# ACS770_breakout_v0_1.net
KiCad netlist of a schematic drawn in EAGLE
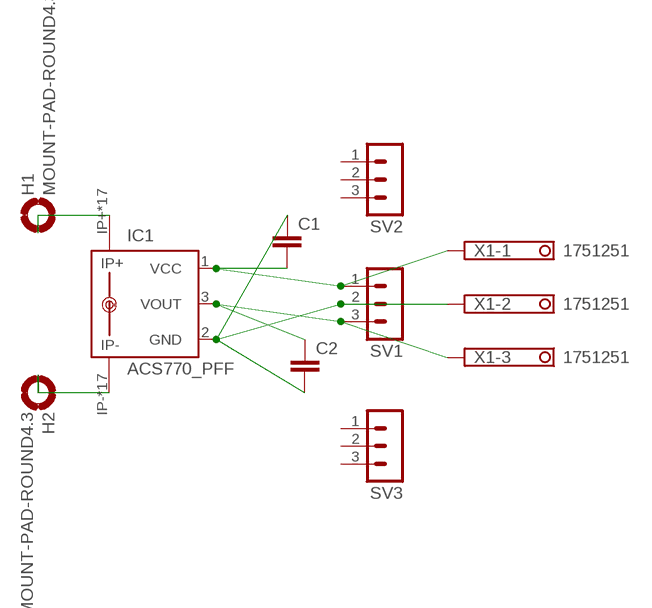
[diagram p0: schematic, sheet 1]

(export (version "E")
  (design (tool "Eeschema 10.0.6"))
  (components
    (comp (ref "C1")
      (value "C-EU025-025X050")
      (footprint "eagle-import:C025-025X050")
      (libsource (lib "eagle-import") (part "C-EU025-025X050"))
    )
    (comp (ref "C2")
      (value "C-EU025-025X050")
      (footprint "eagle-import:C025-025X050")
      (libsource (lib "eagle-import") (part "C-EU025-025X050"))
    )
    (comp (ref "H1")
      (value "MOUNT-PAD-ROUND4.3")
      (footprint "eagle-import:4,3-PAD")
      (libsource (lib "eagle-import") (part "MOUNT-PAD-ROUND4.3"))
    )
    (comp (ref "H2")
      (value "MOUNT-PAD-ROUND4.3")
      (footprint "eagle-import:4,3-PAD")
      (libsource (lib "eagle-import") (part "MOUNT-PAD-ROUND4.3"))
    )
    (comp (ref "IC1")
      (value "ACS770_PFF")
      (footprint "eagle-import:CB-PFF")
      (fields (field (name "MPN") "ACS758LCB-050B-PFF-T"))
      (libsource (lib "eagle-import") (part "ACS758LCB-050B-PFF-T"))
    )
    (comp (ref "SV1")
      (value "MA03-1")
      (footprint "eagle-import:MA03-1")
      (libsource (lib "eagle-import") (part "MA03-1"))
    )
    (comp (ref "SV2")
      (value "MA03-1")
      (footprint "eagle-import:MA03-1")
      (libsource (lib "eagle-import") (part "MA03-1"))
    )
    (comp (ref "SV3")
      (value "MA03-1")
      (footprint "eagle-import:MA03-1")
      (libsource (lib "eagle-import") (part "MA03-1"))
    )
    (comp (ref "X1")
      (value "1751251")
      (footprint "eagle-import:1751251")
      (libsource (lib "eagle-import") (part "1751251"))
    )
  )
  (nets
    (net (code "1") (name "Net-(H1-MOUNT)") (class "Default")
      (node (ref "H1") (pin "B4,3") (pinfunction "MOUNT_B4,3") (pintype "passive"))
      (node (ref "IC1") (pin "IP+") (pinfunction "IP+_IP+") (pintype "passive"))
      (node (ref "IC1") (pin "IP+@10") (pinfunction "IP+_IP+@10") (pintype "passive"))
      (node (ref "IC1") (pin "IP+@11") (pinfunction "IP+_IP+@11") (pintype "passive"))
      (node (ref "IC1") (pin "IP+@12") (pinfunction "IP+_IP+@12") (pintype "passive"))
      (node (ref "IC1") (pin "IP+@13") (pinfunction "IP+_IP+@13") (pintype "passive"))
      (node (ref "IC1") (pin "IP+@14") (pinfunction "IP+_IP+@14") (pintype "passive"))
      (node (ref "IC1") (pin "IP+@15") (pinfunction "IP+_IP+@15") (pintype "passive"))
      (node (ref "IC1") (pin "IP+@16") (pinfunction "IP+_IP+@16") (pintype "passive"))
      (node (ref "IC1") (pin "IP+@17") (pinfunction "IP+_IP+@17") (pintype "passive"))
      (node (ref "IC1") (pin "IP+@2") (pinfunction "IP+_IP+@2") (pintype "passive"))
      (node (ref "IC1") (pin "IP+@3") (pinfunction "IP+_IP+@3") (pintype "passive"))
      (node (ref "IC1") (pin "IP+@4") (pinfunction "IP+_IP+@4") (pintype "passive"))
      (node (ref "IC1") (pin "IP+@5") (pinfunction "IP+_IP+@5") (pintype "passive"))
      (node (ref "IC1") (pin "IP+@6") (pinfunction "IP+_IP+@6") (pintype "passive"))
      (node (ref "IC1") (pin "IP+@7") (pinfunction "IP+_IP+@7") (pintype "passive"))
      (node (ref "IC1") (pin "IP+@8") (pinfunction "IP+_IP+@8") (pintype "passive"))
      (node (ref "IC1") (pin "IP+@9") (pinfunction "IP+_IP+@9") (pintype "passive"))
    )
    (net (code "2") (name "Net-(H2-MOUNT)") (class "Default")
      (node (ref "H2") (pin "B4,3") (pinfunction "MOUNT_B4,3") (pintype "passive"))
      (node (ref "IC1") (pin "IP-") (pinfunction "IP-_IP-") (pintype "passive"))
      (node (ref "IC1") (pin "IP-@10") (pinfunction "IP-_IP-@10") (pintype "passive"))
      (node (ref "IC1") (pin "IP-@11") (pinfunction "IP-_IP-@11") (pintype "passive"))
      (node (ref "IC1") (pin "IP-@12") (pinfunction "IP-_IP-@12") (pintype "passive"))
      (node (ref "IC1") (pin "IP-@13") (pinfunction "IP-_IP-@13") (pintype "passive"))
      (node (ref "IC1") (pin "IP-@14") (pinfunction "IP-_IP-@14") (pintype "passive"))
      (node (ref "IC1") (pin "IP-@15") (pinfunction "IP-_IP-@15") (pintype "passive"))
      (node (ref "IC1") (pin "IP-@16") (pinfunction "IP-_IP-@16") (pintype "passive"))
      (node (ref "IC1") (pin "IP-@17") (pinfunction "IP-_IP-@17") (pintype "passive"))
      (node (ref "IC1") (pin "IP-@2") (pinfunction "IP-_IP-@2") (pintype "passive"))
      (node (ref "IC1") (pin "IP-@3") (pinfunction "IP-_IP-@3") (pintype "passive"))
      (node (ref "IC1") (pin "IP-@4") (pinfunction "IP-_IP-@4") (pintype "passive"))
      (node (ref "IC1") (pin "IP-@5") (pinfunction "IP-_IP-@5") (pintype "passive"))
      (node (ref "IC1") (pin "IP-@6") (pinfunction "IP-_IP-@6") (pintype "passive"))
      (node (ref "IC1") (pin "IP-@7") (pinfunction "IP-_IP-@7") (pintype "passive"))
      (node (ref "IC1") (pin "IP-@8") (pinfunction "IP-_IP-@8") (pintype "passive"))
      (node (ref "IC1") (pin "IP-@9") (pinfunction "IP-_IP-@9") (pintype "passive"))
    )
    (net (code "3") (name "Net-(IC1-GND)") (class "Default")
      (node (ref "C1") (pin "1") (pinfunction "1_1") (pintype "passive"))
      (node (ref "C2") (pin "2") (pinfunction "2_2") (pintype "passive"))
      (node (ref "IC1") (pin "2") (pinfunction "GND_2") (pintype "power_in"))
      (node (ref "SV1") (pin "2") (pinfunction "2_2") (pintype "passive"))
      (node (ref "X1") (pin "2") (pinfunction "K_2") (pintype "passive"))
    )
    (net (code "4") (name "Net-(IC1-VCC)") (class "Default")
      (node (ref "C1") (pin "2") (pinfunction "2_2") (pintype "passive"))
      (node (ref "IC1") (pin "1") (pinfunction "VCC_1") (pintype "power_in"))
      (node (ref "SV1") (pin "1") (pinfunction "1_1") (pintype "passive"))
      (node (ref "X1") (pin "1") (pinfunction "K_1") (pintype "passive"))
    )
    (net (code "5") (name "Net-(IC1-VOUT)") (class "Default")
      (node (ref "C2") (pin "1") (pinfunction "1_1") (pintype "passive"))
      (node (ref "IC1") (pin "3") (pinfunction "VOUT_3") (pintype "output"))
      (node (ref "SV1") (pin "3") (pinfunction "3_3") (pintype "passive"))
      (node (ref "X1") (pin "3") (pinfunction "K_3") (pintype "passive"))
    )
    (net (code "6") (name "unconnected-(SV2-Pad1)") (class "Default")
      (node (ref "SV2") (pin "1") (pinfunction "1_1") (pintype "passive"))
    )
    (net (code "7") (name "unconnected-(SV2-Pad2)") (class "Default")
      (node (ref "SV2") (pin "2") (pinfunction "2_2") (pintype "passive"))
    )
    (net (code "8") (name "unconnected-(SV2-Pad3)") (class "Default")
      (node (ref "SV2") (pin "3") (pinfunction "3_3") (pintype "passive"))
    )
    (net (code "9") (name "unconnected-(SV3-Pad1)") (class "Default")
      (node (ref "SV3") (pin "1") (pinfunction "1_1") (pintype "passive"))
    )
    (net (code "10") (name "unconnected-(SV3-Pad2)") (class "Default")
      (node (ref "SV3") (pin "2") (pinfunction "2_2") (pintype "passive"))
    )
    (net (code "11") (name "unconnected-(SV3-Pad3)") (class "Default")
      (node (ref "SV3") (pin "3") (pinfunction "3_3") (pintype "passive"))
    )
  )
)
